# LED.net
KiCad netlist of a schematic drawn in Altium Designer
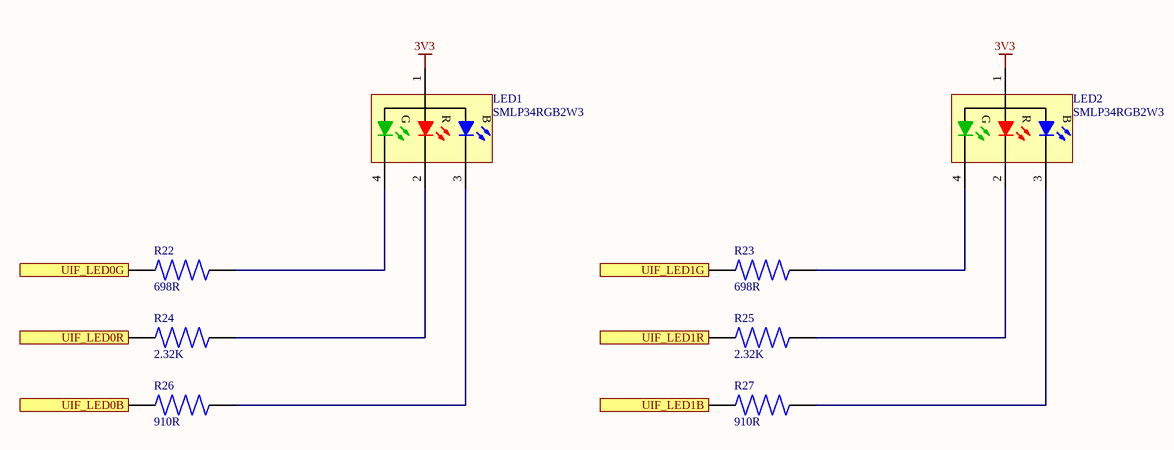
[diagram p0: LED.SchDoc]

(export (version "E")
  (design (tool "Eeschema 10.0.6"))
  (components
    (comp (ref "LED1")
      (value "SMLP34RGB2W3")
      (footprint "ROHM-SMLP34-4_V")
      (description "PICOLED-RGB LED, 5 mA, -40 to 85 degC, 4-Pin 1 x 1 x 0.25 mm SMD, RoHS, Tape and Reel")
      (fields (field (name "MANUFACTURER") "ROHM Semiconductor"))
      (libsource (lib "nnts") (part "SMLP34RGB2W3"))
    )
    (comp (ref "LED2")
      (value "SMLP34RGB2W3")
      (footprint "ROHM-SMLP34-4_V")
      (description "PICOLED-RGB LED, 5 mA, -40 to 85 degC, 4-Pin 1 x 1 x 0.25 mm SMD, RoHS, Tape and Reel")
      (fields (field (name "MANUFACTURER") "ROHM Semiconductor"))
      (libsource (lib "nnts") (part "SMLP34RGB2W3"))
    )
    (comp (ref "R22")
      (value "698R")
      (footprint "R0603 Vishay")
      (description "RES SMD 698 OHM 1% 1/20W 0201")
      (fields
        (field (name "MANUFACTURER") "Vishay")
        (field (name "MANUFACTURER PART NUMBER") "CRCW0201698RFNED")
      )
      (libsource (lib "nnts") (part "CRCW0201698RFNED"))
    )
    (comp (ref "R23")
      (value "698R")
      (footprint "R0603 Vishay")
      (description "RES SMD 698 OHM 1% 1/20W 0201")
      (fields
        (field (name "MANUFACTURER") "Vishay")
        (field (name "MANUFACTURER PART NUMBER") "CRCW0201698RFNED")
      )
      (libsource (lib "nnts") (part "CRCW0201698RFNED"))
    )
    (comp (ref "R24")
      (value "2.32K")
      (footprint "R0805 Vishay")
      (description "VISHAY - CRCW08052K32FKEA - RES, THICK FILM, 2K32, 1%, 0.125W, 0805")
      (fields
        (field (name "MANUFACTURER") "Vishay")
        (field (name "MANUFACTURER PART NUMBER") "CRCW08052K32FKEA")
      )
      (libsource (lib "nnts") (part "CRCW08052K32FKEA"))
    )
    (comp (ref "R25")
      (value "2.32K")
      (footprint "R0805 Vishay")
      (description "VISHAY - CRCW08052K32FKEA - RES, THICK FILM, 2K32, 1%, 0.125W, 0805")
      (fields
        (field (name "MANUFACTURER") "Vishay")
        (field (name "MANUFACTURER PART NUMBER") "CRCW08052K32FKEA")
      )
      (libsource (lib "nnts") (part "CRCW08052K32FKEA"))
    )
    (comp (ref "R26")
      (value "910R")
      (footprint "R0402 Vishay")
      (description "Res Thick Film 0402 910 Ohm 1% 0.063W(1/16W) ±100ppm/C Pad SMD Automotive T/R")
      (fields
        (field (name "MANUFACTURER") "Vishay")
        (field (name "MANUFACTURER PART NUMBER") "CRCW0402910RFKED")
      )
      (libsource (lib "nnts") (part "CRCW0402910RFKED"))
    )
    (comp (ref "R27")
      (value "910R")
      (footprint "R0402 Vishay")
      (description "Res Thick Film 0402 910 Ohm 1% 0.063W(1/16W) ±100ppm/C Pad SMD Automotive T/R")
      (fields
        (field (name "MANUFACTURER") "Vishay")
        (field (name "MANUFACTURER PART NUMBER") "CRCW0402910RFKED")
      )
      (libsource (lib "nnts") (part "CRCW0402910RFKED"))
    )
  )
  (nets
    (net (code "1") (name "/UIF_LED0B") (class "Default")
      (node (ref "R26") (pin "1") (pinfunction "1_1") (pintype "passive"))
    )
    (net (code "2") (name "/UIF_LED0G") (class "Default")
      (node (ref "R22") (pin "1") (pinfunction "1_1") (pintype "passive"))
    )
    (net (code "3") (name "/UIF_LED0R") (class "Default")
      (node (ref "R24") (pin "1") (pinfunction "1_1") (pintype "passive"))
    )
    (net (code "4") (name "/UIF_LED1B") (class "Default")
      (node (ref "R27") (pin "1") (pinfunction "1_1") (pintype "passive"))
    )
    (net (code "5") (name "/UIF_LED1G") (class "Default")
      (node (ref "R23") (pin "1") (pinfunction "1_1") (pintype "passive"))
    )
    (net (code "6") (name "/UIF_LED1R") (class "Default")
      (node (ref "R25") (pin "1") (pinfunction "1_1") (pintype "passive"))
    )
    (net (code "7") (name "3V3") (class "Default")
      (node (ref "LED1") (pin "1") (pinfunction "A_1") (pintype "passive"))
      (node (ref "LED2") (pin "1") (pinfunction "A_1") (pintype "passive"))
    )
    (net (code "8") (name "Net-(LED1-B)") (class "Default")
      (node (ref "LED1") (pin "3") (pinfunction "B_3") (pintype "passive"))
      (node (ref "R26") (pin "2") (pinfunction "2_2") (pintype "passive"))
    )
    (net (code "9") (name "Net-(LED1-G)") (class "Default")
      (node (ref "LED1") (pin "4") (pinfunction "G_4") (pintype "passive"))
      (node (ref "R22") (pin "2") (pinfunction "2_2") (pintype "passive"))
    )
    (net (code "10") (name "Net-(LED1-R)") (class "Default")
      (node (ref "LED1") (pin "2") (pinfunction "R_2") (pintype "passive"))
      (node (ref "R24") (pin "2") (pinfunction "2_2") (pintype "passive"))
    )
    (net (code "11") (name "Net-(LED2-B)") (class "Default")
      (node (ref "LED2") (pin "3") (pinfunction "B_3") (pintype "passive"))
      (node (ref "R27") (pin "2") (pinfunction "2_2") (pintype "passive"))
    )
    (net (code "12") (name "Net-(LED2-G)") (class "Default")
      (node (ref "LED2") (pin "4") (pinfunction "G_4") (pintype "passive"))
      (node (ref "R23") (pin "2") (pinfunction "2_2") (pintype "passive"))
    )
    (net (code "13") (name "Net-(LED2-R)") (class "Default")
      (node (ref "LED2") (pin "2") (pinfunction "R_2") (pintype "passive"))
      (node (ref "R25") (pin "2") (pinfunction "2_2") (pintype "passive"))
    )
  )
)
